# Top.net
KiCad netlist of a schematic drawn in Altium Designer
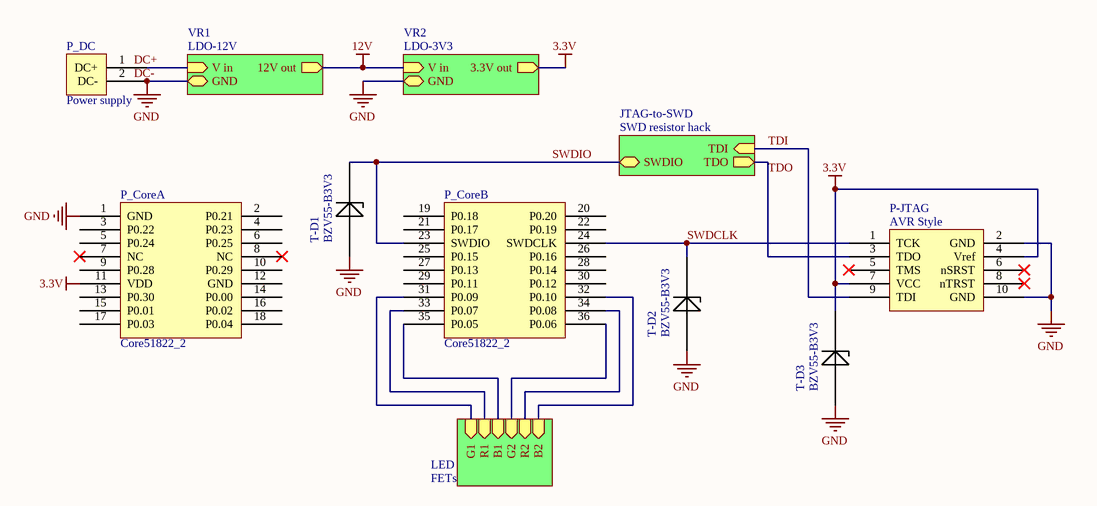
[diagram p0: Top.SchDoc]

(export (version "E")
  (design (tool "Eeschema 10.0.6"))
  (components
    (comp (ref "P-JTAG")
      (value "AVR Style")
      (footprint "Header 2x5 IDC-10S")
      (libsource (lib "Headers") (part "Header JTAG AVR"))
    )
    (comp (ref "P_Core")
      (value "Core51822_2")
      (footprint "Core51822")
      (libsource (lib "Modules") (part "Core51822_2"))
    )
    (comp (ref "P_DC")
      (value "Power supply")
      (footprint "DC cable pad with holes")
      (libsource (lib "Core51822-related") (part "Power supply"))
    )
    (comp (ref "T-D1")
      (value "BZV55-B3V3")
      (footprint "Minimelf")
      (libsource (lib "Standard") (part "Zener Diode"))
    )
    (comp (ref "T-D2")
      (value "BZV55-B3V3")
      (footprint "Minimelf")
      (libsource (lib "Standard") (part "Zener Diode"))
    )
    (comp (ref "T-D3")
      (value "BZV55-B3V3")
      (footprint "Minimelf")
      (libsource (lib "Standard") (part "Zener Diode"))
    )
  )
  (nets
    (net (code "1") (name "/B1") (class "Default")
      (node (ref "P_Core") (pin "35") (pinfunction "P0.05_35") (pintype "passive"))
    )
    (net (code "2") (name "/B2") (class "Default")
      (node (ref "P_Core") (pin "32") (pinfunction "P0.10_32") (pintype "passive"))
    )
    (net (code "5") (name "/G1") (class "Default")
      (node (ref "P_Core") (pin "31") (pinfunction "P0.09_31") (pintype "passive"))
    )
    (net (code "6") (name "/G2") (class "Default")
      (node (ref "P_Core") (pin "36") (pinfunction "P0.06_36") (pintype "passive"))
    )
    (net (code "7") (name "/R1") (class "Default")
      (node (ref "P_Core") (pin "33") (pinfunction "P0.07_33") (pintype "passive"))
    )
    (net (code "8") (name "/R2") (class "Default")
      (node (ref "P_Core") (pin "34") (pinfunction "P0.08_34") (pintype "passive"))
    )
    (net (code "9") (name "/SWDCLK") (class "Default")
      (node (ref "P-JTAG") (pin "1") (pinfunction "TCK_1") (pintype "passive"))
      (node (ref "P_Core") (pin "24") (pinfunction "SWDCLK_24") (pintype "passive"))
      (node (ref "T-D2") (pin "1") (pinfunction "1_1") (pintype "passive"))
    )
    (net (code "10") (name "/SWDIO") (class "Default")
      (node (ref "P_Core") (pin "23") (pinfunction "SWDIO_23") (pintype "passive"))
      (node (ref "T-D1") (pin "1") (pinfunction "1_1") (pintype "passive"))
    )
    (net (code "11") (name "/TDI") (class "Default")
      (node (ref "P-JTAG") (pin "9") (pinfunction "TDI_9") (pintype "passive"))
    )
    (net (code "12") (name "/TDO") (class "Default")
      (node (ref "P-JTAG") (pin "3") (pinfunction "TDO_3") (pintype "passive"))
    )
    (net (code "13") (name "/V in") (class "Default")
      (node (ref "P_DC") (pin "1") (pinfunction "DC+_1") (pintype "passive"))
    )
    (net (code "14") (name "3.3V") (class "Default")
      (node (ref "P-JTAG") (pin "4") (pinfunction "Vref_4") (pintype "passive"))
      (node (ref "P-JTAG") (pin "7") (pinfunction "VCC_7") (pintype "passive"))
      (node (ref "P_Core") (pin "11") (pinfunction "VDD_11") (pintype "passive"))
      (node (ref "T-D3") (pin "1") (pinfunction "1_1") (pintype "passive"))
    )
    (net (code "16") (name "GND") (class "Default")
      (node (ref "P-JTAG") (pin "10") (pinfunction "GND_10") (pintype "passive"))
      (node (ref "P-JTAG") (pin "2") (pinfunction "GND_2") (pintype "passive"))
      (node (ref "P_Core") (pin "1") (pinfunction "GND_1") (pintype "passive"))
      (node (ref "P_DC") (pin "2") (pinfunction "DC-_2") (pintype "passive"))
      (node (ref "T-D1") (pin "2") (pinfunction "2_2") (pintype "passive"))
      (node (ref "T-D2") (pin "2") (pinfunction "2_2") (pintype "passive"))
      (node (ref "T-D3") (pin "2") (pinfunction "2_2") (pintype "passive"))
    )
    (net (code "17") (name "unconnected-(P-JTAG-TMS-Pad5)") (class "Default")
      (node (ref "P-JTAG") (pin "5") (pinfunction "TMS_5") (pintype "passive+no_connect"))
    )
    (net (code "18") (name "unconnected-(P-JTAG-nSRST-Pad6)") (class "Default")
      (node (ref "P-JTAG") (pin "6") (pinfunction "nSRST_6") (pintype "passive+no_connect"))
    )
    (net (code "19") (name "unconnected-(P-JTAG-nTRST-Pad8)") (class "Default")
      (node (ref "P-JTAG") (pin "8") (pinfunction "nTRST_8") (pintype "passive+no_connect"))
    )
    (net (code "20") (name "unconnected-(P_CoreA-GND-Pad12)") (class "Default")
      (node (ref "P_Core") (pin "12") (pinfunction "GND_12") (pintype "passive"))
    )
    (net (code "21") (name "unconnected-(P_CoreA-NC-Pad7)") (class "Default")
      (node (ref "P_Core") (pin "7") (pinfunction "NC_7") (pintype "passive+no_connect"))
    )
    (net (code "22") (name "unconnected-(P_CoreA-NC-Pad8)") (class "Default")
      (node (ref "P_Core") (pin "8") (pinfunction "NC_8") (pintype "passive+no_connect"))
    )
    (net (code "23") (name "unconnected-(P_CoreA-P0.00-Pad14)") (class "Default")
      (node (ref "P_Core") (pin "14") (pinfunction "P0.00_14") (pintype "passive"))
    )
    (net (code "24") (name "unconnected-(P_CoreA-P0.01-Pad15)") (class "Default")
      (node (ref "P_Core") (pin "15") (pinfunction "P0.01_15") (pintype "passive"))
    )
    (net (code "25") (name "unconnected-(P_CoreA-P0.02-Pad16)") (class "Default")
      (node (ref "P_Core") (pin "16") (pinfunction "P0.02_16") (pintype "passive"))
    )
    (net (code "26") (name "unconnected-(P_CoreA-P0.03-Pad17)") (class "Default")
      (node (ref "P_Core") (pin "17") (pinfunction "P0.03_17") (pintype "passive"))
    )
    (net (code "27") (name "unconnected-(P_CoreA-P0.04-Pad18)") (class "Default")
      (node (ref "P_Core") (pin "18") (pinfunction "P0.04_18") (pintype "passive"))
    )
    (net (code "28") (name "unconnected-(P_CoreA-P0.21-Pad2)") (class "Default")
      (node (ref "P_Core") (pin "2") (pinfunction "P0.21_2") (pintype "passive"))
    )
    (net (code "29") (name "unconnected-(P_CoreA-P0.22-Pad3)") (class "Default")
      (node (ref "P_Core") (pin "3") (pinfunction "P0.22_3") (pintype "power_in"))
    )
    (net (code "30") (name "unconnected-(P_CoreA-P0.23-Pad4)") (class "Default")
      (node (ref "P_Core") (pin "4") (pinfunction "P0.23_4") (pintype "passive"))
    )
    (net (code "31") (name "unconnected-(P_CoreA-P0.24-Pad5)") (class "Default")
      (node (ref "P_Core") (pin "5") (pinfunction "P0.24_5") (pintype "passive"))
    )
    (net (code "32") (name "unconnected-(P_CoreA-P0.25-Pad6)") (class "Default")
      (node (ref "P_Core") (pin "6") (pinfunction "P0.25_6") (pintype "passive"))
    )
    (net (code "33") (name "unconnected-(P_CoreA-P0.28-Pad9)") (class "Default")
      (node (ref "P_Core") (pin "9") (pinfunction "P0.28_9") (pintype "passive"))
    )
    (net (code "34") (name "unconnected-(P_CoreA-P0.29-Pad10)") (class "Default")
      (node (ref "P_Core") (pin "10") (pinfunction "P0.29_10") (pintype "passive"))
    )
    (net (code "35") (name "unconnected-(P_CoreA-P0.30-Pad13)") (class "Default")
      (node (ref "P_Core") (pin "13") (pinfunction "P0.30_13") (pintype "passive"))
    )
    (net (code "36") (name "unconnected-(P_CoreB-P0.11-Pad29)") (class "Default")
      (node (ref "P_Core") (pin "29") (pinfunction "P0.11_29") (pintype "passive"))
    )
    (net (code "37") (name "unconnected-(P_CoreB-P0.12-Pad30)") (class "Default")
      (node (ref "P_Core") (pin "30") (pinfunction "P0.12_30") (pintype "passive"))
    )
    (net (code "38") (name "unconnected-(P_CoreB-P0.13-Pad27)") (class "Default")
      (node (ref "P_Core") (pin "27") (pinfunction "P0.13_27") (pintype "passive"))
    )
    (net (code "39") (name "unconnected-(P_CoreB-P0.14-Pad28)") (class "Default")
      (node (ref "P_Core") (pin "28") (pinfunction "P0.14_28") (pintype "passive"))
    )
    (net (code "40") (name "unconnected-(P_CoreB-P0.15-Pad25)") (class "Default")
      (node (ref "P_Core") (pin "25") (pinfunction "P0.15_25") (pintype "passive"))
    )
    (net (code "41") (name "unconnected-(P_CoreB-P0.16-Pad26)") (class "Default")
      (node (ref "P_Core") (pin "26") (pinfunction "P0.16_26") (pintype "passive"))
    )
    (net (code "42") (name "unconnected-(P_CoreB-P0.17-Pad21)") (class "Default")
      (node (ref "P_Core") (pin "21") (pinfunction "P0.17_21") (pintype "power_in"))
    )
    (net (code "43") (name "unconnected-(P_CoreB-P0.18-Pad19)") (class "Default")
      (node (ref "P_Core") (pin "19") (pinfunction "P0.18_19") (pintype "passive"))
    )
    (net (code "44") (name "unconnected-(P_CoreB-P0.19-Pad22)") (class "Default")
      (node (ref "P_Core") (pin "22") (pinfunction "P0.19_22") (pintype "passive"))
    )
    (net (code "45") (name "unconnected-(P_CoreB-P0.20-Pad20)") (class "Default")
      (node (ref "P_Core") (pin "20") (pinfunction "P0.20_20") (pintype "passive"))
    )
  )
)
